# ProPrj_Arduino_DengDog_2025-10-27.net
KiCad netlist of a schematic drawn in EasyEDA Pro
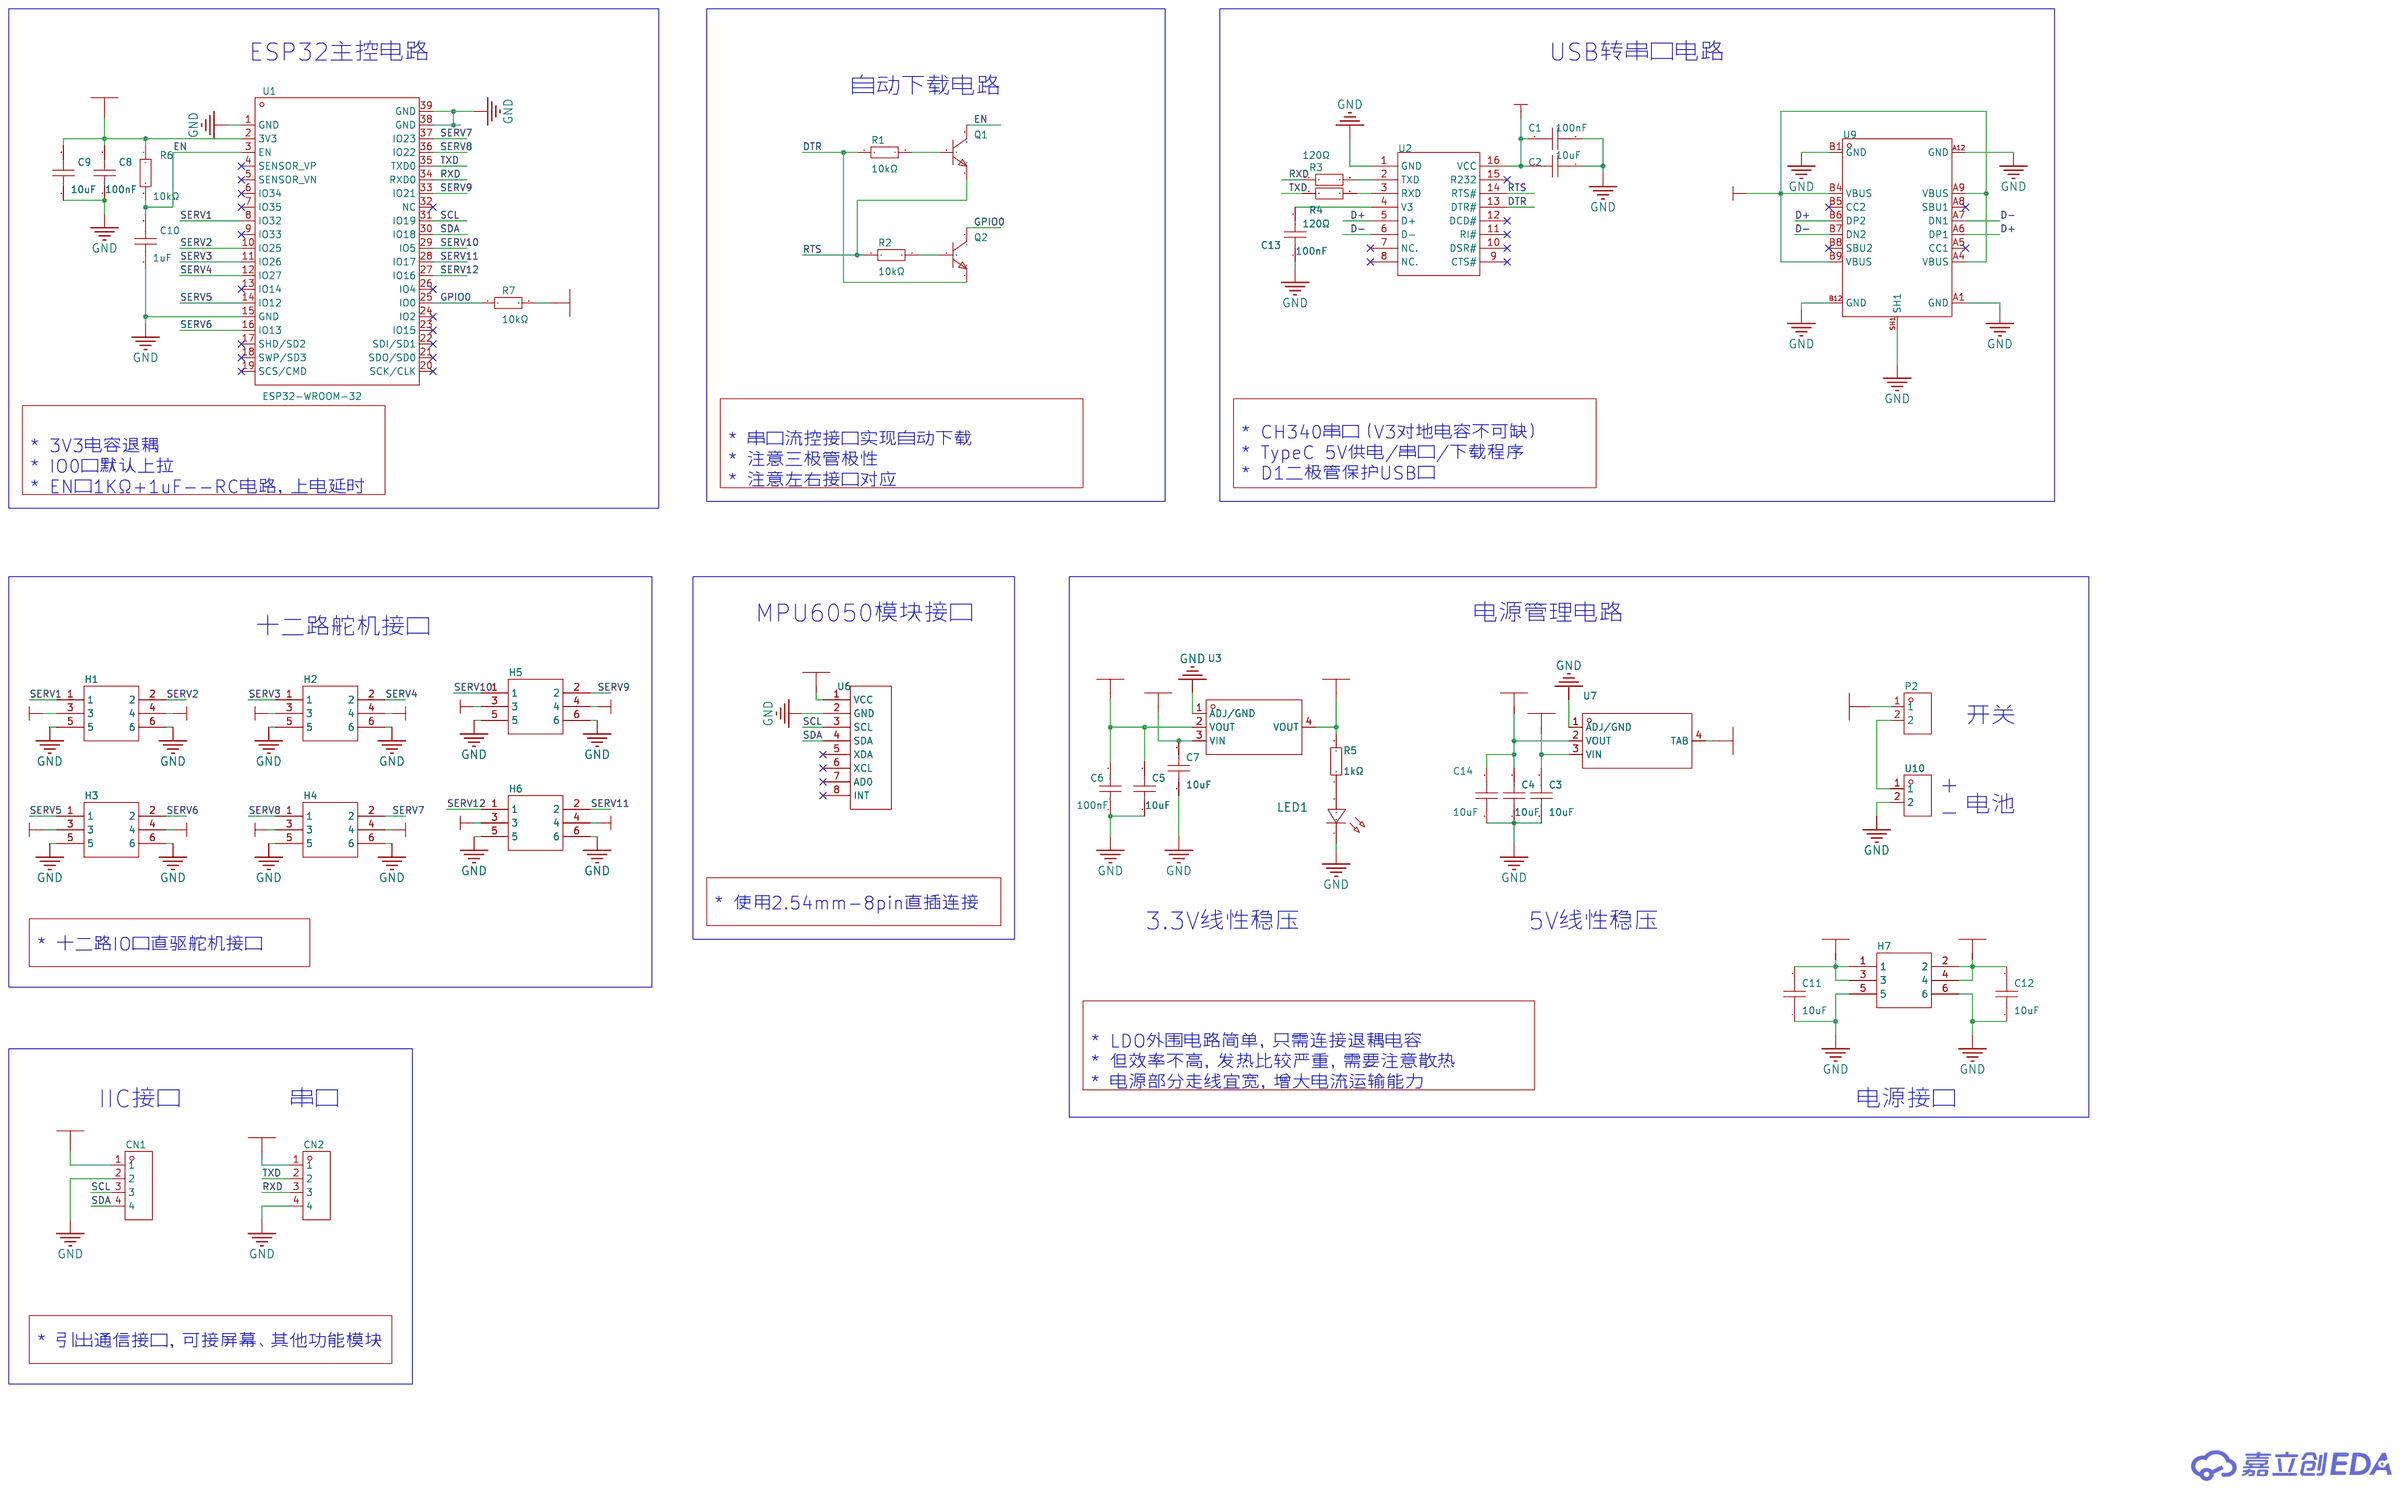
[diagram p0: schematic sheet]

(export (version "E")
  (design (tool "Eeschema 10.0.6"))
  (components
    (comp (ref "C1")
      (value "100nF")
      (fields
        (field (name "Manufacturer Part") "CC0603KRX7R9BB104")
        (field (name "Manufacturer") "YAGEO(国巨)")
      )
      (libsource (lib "easyedapro") (part "C1210X7R475K630NT"))
    )
    (comp (ref "C2")
      (value "10uF")
      (fields
        (field (name "Manufacturer Part") "CL10A106KP8NNNC")
        (field (name "Manufacturer") "SAMSUNG(三星)")
      )
      (libsource (lib "easyedapro") (part "C1210X7R475K630NT"))
    )
    (comp (ref "C3")
      (value "10uF")
      (fields
        (field (name "Manufacturer Part") "CL10A106KP8NNNC")
        (field (name "Manufacturer") "SAMSUNG(三星)")
      )
      (libsource (lib "easyedapro") (part "C1210X7R475K630NT"))
    )
    (comp (ref "C4")
      (value "10uF")
      (fields
        (field (name "Manufacturer Part") "CL10A106KP8NNNC")
        (field (name "Manufacturer") "SAMSUNG(三星)")
      )
      (libsource (lib "easyedapro") (part "C1210X7R475K630NT"))
    )
    (comp (ref "C5")
      (value "10uF")
      (fields
        (field (name "Manufacturer Part") "CL10A106KP8NNNC")
        (field (name "Manufacturer") "SAMSUNG(三星)")
      )
      (libsource (lib "easyedapro") (part "C1210X7R475K630NT"))
    )
    (comp (ref "C6")
      (value "100nF")
      (fields
        (field (name "Manufacturer Part") "CC0603KRX7R9BB104")
        (field (name "Manufacturer") "YAGEO(国巨)")
      )
      (libsource (lib "easyedapro") (part "C1210X7R475K630NT"))
    )
    (comp (ref "C7")
      (value "10uF")
      (fields
        (field (name "Manufacturer Part") "CL10A106KP8NNNC")
        (field (name "Manufacturer") "SAMSUNG(三星)")
      )
      (libsource (lib "easyedapro") (part "C1210X7R475K630NT"))
    )
    (comp (ref "C8")
      (value "100nF")
      (fields
        (field (name "Manufacturer Part") "CC0603KRX7R9BB104")
        (field (name "Manufacturer") "YAGEO(国巨)")
      )
      (libsource (lib "easyedapro") (part "C1210X7R475K630NT"))
    )
    (comp (ref "C9")
      (value "10uF")
      (fields
        (field (name "Manufacturer Part") "CL10A106KP8NNNC")
        (field (name "Manufacturer") "SAMSUNG(三星)")
      )
      (libsource (lib "easyedapro") (part "C1210X7R475K630NT"))
    )
    (comp (ref "C10")
      (value "1uF")
      (fields
        (field (name "Manufacturer Part") "CL10A105KB8NNNC")
        (field (name "Manufacturer") "SAMSUNG(三星)")
      )
      (libsource (lib "easyedapro") (part "C1210X7R475K630NT"))
    )
    (comp (ref "C11")
      (value "10uF")
      (fields
        (field (name "Manufacturer Part") "CL10A106KP8NNNC")
        (field (name "Manufacturer") "SAMSUNG(三星)")
      )
      (libsource (lib "easyedapro") (part "C1210X7R475K630NT"))
    )
    (comp (ref "C12")
      (value "10uF")
      (fields
        (field (name "Manufacturer Part") "CL10A106KP8NNNC")
        (field (name "Manufacturer") "SAMSUNG(三星)")
      )
      (libsource (lib "easyedapro") (part "C1210X7R475K630NT"))
    )
    (comp (ref "C13")
      (value "100nF")
      (fields
        (field (name "Manufacturer Part") "CC0603KRX7R9BB104")
        (field (name "Manufacturer") "YAGEO(国巨)")
      )
      (libsource (lib "easyedapro") (part "C1210X7R475K630NT"))
    )
    (comp (ref "C14")
      (value "10uF")
      (fields
        (field (name "Manufacturer Part") "CL10A106KP8NNNC")
        (field (name "Manufacturer") "SAMSUNG(三星)")
      )
      (libsource (lib "easyedapro") (part "C1210X7R475K630NT"))
    )
    (comp (ref "CN1")
      (value "A2541WV-4P")
      (footprint "easyedapro:HDR-TH_4P-P2.54-V-M")
      (fields (field (name "Manufacturer") "CJT(长江连接器)"))
      (libsource (lib "easyedapro") (part "A2541WV-4P_C5346656"))
    )
    (comp (ref "CN2")
      (value "A2541WV-4P")
      (footprint "easyedapro:HDR-TH_4P-P2.54-V-M")
      (fields (field (name "Manufacturer") "CJT(长江连接器)"))
      (libsource (lib "easyedapro") (part "A2541WV-4P_C5346656"))
    )
    (comp (ref "H1")
      (value "A2541WV-2x3P")
      (footprint "easyedapro:HDR-TH_6P-P2.54-V-R2-C3-S2.54_A2541WV-2X3P")
      (fields (field (name "Manufacturer") "CJT(长江连接器)"))
      (libsource (lib "easyedapro") (part "A2541WV-2X3P"))
    )
    (comp (ref "H2")
      (value "A2541WV-2x3P")
      (footprint "easyedapro:HDR-TH_6P-P2.54-V-R2-C3-S2.54_A2541WV-2X3P")
      (fields (field (name "Manufacturer") "CJT(长江连接器)"))
      (libsource (lib "easyedapro") (part "A2541WV-2X3P"))
    )
    (comp (ref "H3")
      (value "A2541WV-2x3P")
      (footprint "easyedapro:HDR-TH_6P-P2.54-V-R2-C3-S2.54_A2541WV-2X3P")
      (fields (field (name "Manufacturer") "CJT(长江连接器)"))
      (libsource (lib "easyedapro") (part "A2541WV-2X3P"))
    )
    (comp (ref "H4")
      (value "A2541WV-2x3P")
      (footprint "easyedapro:HDR-TH_6P-P2.54-V-R2-C3-S2.54_A2541WV-2X3P")
      (fields (field (name "Manufacturer") "CJT(长江连接器)"))
      (libsource (lib "easyedapro") (part "A2541WV-2X3P"))
    )
    (comp (ref "H5")
      (value "A2541WV-2x3P")
      (footprint "easyedapro:HDR-TH_6P-P2.54-V-R2-C3-S2.54_A2541WV-2X3P")
      (fields (field (name "Manufacturer") "CJT(长江连接器)"))
      (libsource (lib "easyedapro") (part "A2541WV-2X3P"))
    )
    (comp (ref "H6")
      (value "A2541WV-2x3P")
      (footprint "easyedapro:HDR-TH_6P-P2.54-V-R2-C3-S2.54_A2541WV-2X3P")
      (fields (field (name "Manufacturer") "CJT(长江连接器)"))
      (libsource (lib "easyedapro") (part "A2541WV-2X3P"))
    )
    (comp (ref "H7")
      (value "A2541WV-2x3P")
      (footprint "easyedapro:HDR-TH_6P-P2.54-V-R2-C3-S2.54_A2541WV-2X3P")
      (fields (field (name "Manufacturer") "CJT(长江连接器)"))
      (libsource (lib "easyedapro") (part "A2541WV-2X3P"))
    )
    (comp (ref "LED1")
      (value "19-217/R6C-AL1M2VY/3T")
      (fields (field (name "Manufacturer") "EVERLIGHT(亿光)"))
      (libsource (lib "easyedapro") (part "LED_R"))
    )
    (comp (ref "P2")
      (value "KF301-5.0-2P")
      (footprint "easyedapro:CONN-TH_EK508V-02P")
      (fields (field (name "Manufacturer") "KEFA(科发)"))
      (libsource (lib "easyedapro") (part "EK508V-02P_C9900003719"))
    )
    (comp (ref "Q1")
      (value "2N3904S-RTK/PS")
      (fields (field (name "Manufacturer") "KEC"))
      (libsource (lib "easyedapro") (part "2N3904(SOT-23)"))
    )
    (comp (ref "Q2")
      (value "2N3904S-RTK/PS")
      (fields (field (name "Manufacturer") "KEC"))
      (libsource (lib "easyedapro") (part "2N3904(SOT-23)"))
    )
    (comp (ref "R1")
      (value "10kΩ")
      (fields
        (field (name "Manufacturer Part") "0603WAF1002T5E")
        (field (name "Manufacturer") "UNI-ROYAL(厚声)")
      )
      (libsource (lib "easyedapro") (part "电阻"))
    )
    (comp (ref "R2")
      (value "10kΩ")
      (fields
        (field (name "Manufacturer Part") "0603WAF1002T5E")
        (field (name "Manufacturer") "UNI-ROYAL(厚声)")
      )
      (libsource (lib "easyedapro") (part "电阻"))
    )
    (comp (ref "R3")
      (value "120Ω")
      (fields
        (field (name "Manufacturer Part") "0603WAF1200T5E")
        (field (name "Manufacturer") "UNI-ROYAL(厚声)")
      )
      (libsource (lib "easyedapro") (part "电阻"))
    )
    (comp (ref "R4")
      (value "120Ω")
      (fields
        (field (name "Manufacturer Part") "0603WAF1200T5E")
        (field (name "Manufacturer") "UNI-ROYAL(厚声)")
      )
      (libsource (lib "easyedapro") (part "电阻"))
    )
    (comp (ref "R5")
      (value "1kΩ")
      (fields
        (field (name "Manufacturer Part") "0603WAF1001T5E")
        (field (name "Manufacturer") "UNI-ROYAL(厚声)")
      )
      (libsource (lib "easyedapro") (part "电阻"))
    )
    (comp (ref "R6")
      (value "10kΩ")
      (fields
        (field (name "Manufacturer Part") "0603WAF1002T5E")
        (field (name "Manufacturer") "UNI-ROYAL(厚声)")
      )
      (libsource (lib "easyedapro") (part "电阻"))
    )
    (comp (ref "R7")
      (value "10kΩ")
      (fields
        (field (name "Manufacturer Part") "0603WAF1002T5E")
        (field (name "Manufacturer") "UNI-ROYAL(厚声)")
      )
      (libsource (lib "easyedapro") (part "电阻"))
    )
    (comp (ref "U1")
      (value "ESP32-WROOM-32")
      (footprint "easyedapro:WIFIM-SMD_ESP-32S")
      (libsource (lib "easyedapro") (part "ESP32-WROOM-32"))
    )
    (comp (ref "U2")
      (value "CH340C")
      (fields (field (name "Manufacturer") "WCH(南京沁恒)"))
      (libsource (lib "easyedapro") (part "CH340C"))
    )
    (comp (ref "U3")
      (value "AMS1117-3.3")
      (fields (field (name "Manufacturer") "AMS"))
      (libsource (lib "easyedapro") (part "AMS1117-3.3V"))
    )
    (comp (ref "U6")
      (value "~")
      (footprint "easyedapro:MPU6050")
      (libsource (lib "easyedapro") (part "MPU6050"))
    )
    (comp (ref "U7")
      (value "~")
      (footprint "easyedapro:TO-263-3_L8.6-W10.2-P2.54-LS14.4-TL")
      (description "输出类型:固定;输出极性:正;输出通道数:1;最大输入电压:12V;输出电压:5V;压差:1.5V@(5A);输出电流:5A;电源纹波抑制比(PRSS):72dB@(120Hz);")
      (fields (field (name "Manufacturer Part") "LM1084S-5.0/TR") (field (name "Manufacturer") "HGSEMI(华冠)"))
      (libsource (lib "easyedapro") (part "LM1084S-5.0/TR"))
    )
    (comp (ref "U9")
      (value "U263-163N-4OS1735")
      (footprint "easyedapro:USB-C-SMD_U263-163N-4GS1735")
      (fields (field (name "Manufacturer") "XKB Connectivity(中国星坤)"))
      (libsource (lib "easyedapro") (part "U263-163N-4OS1735"))
    )
    (comp (ref "U10")
      (value "KF301-5.0-2P")
      (footprint "easyedapro:CONN-TH_P5.00_KF301-5.0-2P")
      (description "间距:5mm;排数:1;每排PIN数:2;安装方式:直针;额定电流:17A;额定电压:250V;线规 - AWG:14~22;线规 - mm?:1.5;工作温度范围:-30~+120;颜色:蓝色;")
      (fields (field (name "Manufacturer") "KEFA(科发)"))
      (libsource (lib "easyedapro") (part "KF301-5.0-2P"))
    )
  )
  (nets
    (net (code "1") (name "/D+") (class "Default")
      (node (ref "U2") (pin "5") (pinfunction "D+_5") (pintype "unspecified"))
      (node (ref "U9") (pin "A6") (pinfunction "DP1_A6") (pintype "input"))
      (node (ref "U9") (pin "B6") (pinfunction "DP2_B6") (pintype "input"))
    )
    (net (code "2") (name "/D-") (class "Default")
      (node (ref "U2") (pin "6") (pinfunction "D-_6") (pintype "unspecified"))
      (node (ref "U9") (pin "A7") (pinfunction "DN1_A7") (pintype "input"))
      (node (ref "U9") (pin "B7") (pinfunction "DN2_B7") (pintype "input"))
    )
    (net (code "3") (name "/DTR") (class "Default")
      (node (ref "Q2") (pin "1") (pinfunction "E_1") (pintype "input"))
      (node (ref "R1") (pin "1") (pinfunction "1_1") (pintype "input"))
      (node (ref "U2") (pin "13") (pinfunction "DTR#_13") (pintype "unspecified"))
    )
    (net (code "4") (name "/EN") (class "Default")
      (node (ref "C10") (pin "2") (pinfunction "2_2") (pintype "input"))
      (node (ref "Q1") (pin "3") (pinfunction "C_3") (pintype "input"))
      (node (ref "R6") (pin "2") (pinfunction "2_2") (pintype "input"))
      (node (ref "U1") (pin "3") (pinfunction "EN_3") (pintype "unspecified"))
    )
    (net (code "5") (name "/GPIO0") (class "Default")
      (node (ref "Q2") (pin "3") (pinfunction "C_3") (pintype "input"))
      (node (ref "R7") (pin "1") (pinfunction "1_1") (pintype "input"))
      (node (ref "U1") (pin "25") (pinfunction "IO0_25") (pintype "unspecified"))
    )
    (net (code "6") (name "/RTS") (class "Default")
      (node (ref "Q1") (pin "1") (pinfunction "E_1") (pintype "input"))
      (node (ref "R2") (pin "1") (pinfunction "1_1") (pintype "input"))
      (node (ref "U2") (pin "14") (pinfunction "RTS#_14") (pintype "unspecified"))
    )
    (net (code "7") (name "/RXD") (class "Default")
      (node (ref "CN2") (pin "3") (pinfunction "3_3") (pintype "input"))
      (node (ref "R3") (pin "1") (pinfunction "1_1") (pintype "input"))
      (node (ref "U1") (pin "34") (pinfunction "RXD0_34") (pintype "unspecified"))
    )
    (net (code "8") (name "/SCL") (class "Default")
      (node (ref "CN1") (pin "3") (pinfunction "3_3") (pintype "input"))
      (node (ref "U1") (pin "31") (pinfunction "IO19_31") (pintype "unspecified"))
      (node (ref "U6") (pin "3") (pinfunction "SCL_3") (pintype "input"))
    )
    (net (code "9") (name "/SDA") (class "Default")
      (node (ref "CN1") (pin "4") (pinfunction "4_4") (pintype "input"))
      (node (ref "U1") (pin "30") (pinfunction "IO18_30") (pintype "unspecified"))
      (node (ref "U6") (pin "4") (pinfunction "SDA_4") (pintype "input"))
    )
    (net (code "10") (name "/SERV1") (class "Default")
      (node (ref "H1") (pin "1") (pinfunction "1_1") (pintype "input"))
      (node (ref "U1") (pin "8") (pinfunction "IO32_8") (pintype "unspecified"))
    )
    (net (code "11") (name "/SERV2") (class "Default")
      (node (ref "H1") (pin "2") (pinfunction "2_2") (pintype "input"))
      (node (ref "U1") (pin "10") (pinfunction "IO25_10") (pintype "unspecified"))
    )
    (net (code "12") (name "/SERV3") (class "Default")
      (node (ref "H2") (pin "1") (pinfunction "1_1") (pintype "input"))
      (node (ref "U1") (pin "11") (pinfunction "IO26_11") (pintype "unspecified"))
    )
    (net (code "13") (name "/SERV4") (class "Default")
      (node (ref "H2") (pin "2") (pinfunction "2_2") (pintype "input"))
      (node (ref "U1") (pin "12") (pinfunction "IO27_12") (pintype "unspecified"))
    )
    (net (code "14") (name "/SERV5") (class "Default")
      (node (ref "H3") (pin "1") (pinfunction "1_1") (pintype "input"))
      (node (ref "U1") (pin "14") (pinfunction "IO12_14") (pintype "unspecified"))
    )
    (net (code "15") (name "/SERV6") (class "Default")
      (node (ref "H3") (pin "2") (pinfunction "2_2") (pintype "input"))
      (node (ref "U1") (pin "16") (pinfunction "IO13_16") (pintype "unspecified"))
    )
    (net (code "16") (name "/SERV7") (class "Default")
      (node (ref "H4") (pin "2") (pinfunction "2_2") (pintype "input"))
      (node (ref "U1") (pin "37") (pinfunction "IO23_37") (pintype "unspecified"))
    )
    (net (code "17") (name "/SERV8") (class "Default")
      (node (ref "H4") (pin "1") (pinfunction "1_1") (pintype "input"))
      (node (ref "U1") (pin "36") (pinfunction "IO22_36") (pintype "unspecified"))
    )
    (net (code "18") (name "/SERV9") (class "Default")
      (node (ref "H5") (pin "2") (pinfunction "2_2") (pintype "input"))
      (node (ref "U1") (pin "33") (pinfunction "IO21_33") (pintype "unspecified"))
    )
    (net (code "19") (name "/SERV10") (class "Default")
      (node (ref "H5") (pin "1") (pinfunction "1_1") (pintype "input"))
      (node (ref "U1") (pin "29") (pinfunction "IO5_29") (pintype "unspecified"))
    )
    (net (code "20") (name "/SERV11") (class "Default")
      (node (ref "H6") (pin "2") (pinfunction "2_2") (pintype "input"))
      (node (ref "U1") (pin "28") (pinfunction "IO17_28") (pintype "unspecified"))
    )
    (net (code "21") (name "/SERV12") (class "Default")
      (node (ref "H6") (pin "1") (pinfunction "1_1") (pintype "input"))
      (node (ref "U1") (pin "27") (pinfunction "IO16_27") (pintype "unspecified"))
    )
    (net (code "22") (name "/TXD") (class "Default")
      (node (ref "CN2") (pin "2") (pinfunction "2_2") (pintype "input"))
      (node (ref "R4") (pin "1") (pinfunction "1_1") (pintype "input"))
      (node (ref "U1") (pin "35") (pinfunction "TXD0_35") (pintype "unspecified"))
    )
    (net (code "23") (name "3V3") (class "Default")
      (node (ref "C11") (pin "2") (pinfunction "2_2") (pintype "input"))
      (node (ref "C5") (pin "2") (pinfunction "2_2") (pintype "input"))
      (node (ref "C6") (pin "2") (pinfunction "2_2") (pintype "input"))
      (node (ref "C8") (pin "2") (pinfunction "2_2") (pintype "input"))
      (node (ref "C9") (pin "2") (pinfunction "2_2") (pintype "input"))
      (node (ref "CN1") (pin "1") (pinfunction "1_1") (pintype "input"))
      (node (ref "H7") (pin "1") (pinfunction "1_1") (pintype "input"))
      (node (ref "H7") (pin "3") (pinfunction "3_3") (pintype "input"))
      (node (ref "R5") (pin "2") (pinfunction "2_2") (pintype "input"))
      (node (ref "R6") (pin "1") (pinfunction "1_1") (pintype "input"))
      (node (ref "R7") (pin "2") (pinfunction "2_2") (pintype "input"))
      (node (ref "U1") (pin "2") (pinfunction "3V3_2") (pintype "unspecified"))
      (node (ref "U3") (pin "2") (pinfunction "VOUT_2") (pintype "unspecified"))
      (node (ref "U3") (pin "4") (pinfunction "VOUT_4") (pintype "unspecified"))
      (node (ref "U6") (pin "1") (pinfunction "VCC_1") (pintype "input"))
    )
    (net (code "24") (name "5VIN") (class "Default")
      (node (ref "C1") (pin "1") (pinfunction "1_1") (pintype "input"))
      (node (ref "C12") (pin "2") (pinfunction "2_2") (pintype "input"))
      (node (ref "C14") (pin "2") (pinfunction "2_2") (pintype "input"))
      (node (ref "C2") (pin "1") (pinfunction "1_1") (pintype "input"))
      (node (ref "C4") (pin "2") (pinfunction "2_2") (pintype "input"))
      (node (ref "C7") (pin "2") (pinfunction "2_2") (pintype "input"))
      (node (ref "CN2") (pin "1") (pinfunction "1_1") (pintype "input"))
      (node (ref "H1") (pin "3") (pinfunction "3_3") (pintype "input"))
      (node (ref "H1") (pin "4") (pinfunction "4_4") (pintype "input"))
      (node (ref "H2") (pin "3") (pinfunction "3_3") (pintype "input"))
      (node (ref "H2") (pin "4") (pinfunction "4_4") (pintype "input"))
      (node (ref "H3") (pin "3") (pinfunction "3_3") (pintype "input"))
      (node (ref "H3") (pin "4") (pinfunction "4_4") (pintype "input"))
      (node (ref "H4") (pin "3") (pinfunction "3_3") (pintype "input"))
      (node (ref "H4") (pin "4") (pinfunction "4_4") (pintype "input"))
      (node (ref "H5") (pin "3") (pinfunction "3_3") (pintype "input"))
      (node (ref "H5") (pin "4") (pinfunction "4_4") (pintype "input"))
      (node (ref "H6") (pin "3") (pinfunction "3_3") (pintype "input"))
      (node (ref "H6") (pin "4") (pinfunction "4_4") (pintype "input"))
      (node (ref "H7") (pin "2") (pinfunction "2_2") (pintype "input"))
      (node (ref "H7") (pin "4") (pinfunction "4_4") (pintype "input"))
      (node (ref "U2") (pin "16") (pinfunction "VCC_16") (pintype "unspecified"))
      (node (ref "U3") (pin "3") (pinfunction "VIN_3") (pintype "unspecified"))
      (node (ref "U7") (pin "2") (pinfunction "VOUT_2") (pintype "input"))
      (node (ref "U7") (pin "4") (pinfunction "TAB_4") (pintype "input"))
      (node (ref "U9") (pin "A4") (pinfunction "VBUS_A4") (pintype "input"))
      (node (ref "U9") (pin "A9") (pinfunction "VBUS_A9") (pintype "input"))
      (node (ref "U9") (pin "B4") (pinfunction "VBUS_B4") (pintype "input"))
      (node (ref "U9") (pin "B9") (pinfunction "VBUS_B9") (pintype "input"))
    )
    (net (code "25") (name "GND") (class "Default")
      (node (ref "C1") (pin "2") (pinfunction "2_2") (pintype "input"))
      (node (ref "C10") (pin "1") (pinfunction "1_1") (pintype "input"))
      (node (ref "C11") (pin "1") (pinfunction "1_1") (pintype "input"))
      (node (ref "C12") (pin "1") (pinfunction "1_1") (pintype "input"))
      (node (ref "C13") (pin "1") (pinfunction "1_1") (pintype "input"))
      (node (ref "C14") (pin "1") (pinfunction "1_1") (pintype "input"))
      (node (ref "C2") (pin "2") (pinfunction "2_2") (pintype "input"))
      (node (ref "C3") (pin "1") (pinfunction "1_1") (pintype "input"))
      (node (ref "C4") (pin "1") (pinfunction "1_1") (pintype "input"))
      (node (ref "C5") (pin "1") (pinfunction "1_1") (pintype "input"))
      (node (ref "C6") (pin "1") (pinfunction "1_1") (pintype "input"))
      (node (ref "C7") (pin "1") (pinfunction "1_1") (pintype "input"))
      (node (ref "C8") (pin "1") (pinfunction "1_1") (pintype "input"))
      (node (ref "C9") (pin "1") (pinfunction "1_1") (pintype "input"))
      (node (ref "CN1") (pin "2") (pinfunction "2_2") (pintype "input"))
      (node (ref "CN2") (pin "4") (pinfunction "4_4") (pintype "input"))
      (node (ref "H1") (pin "5") (pinfunction "5_5") (pintype "input"))
      (node (ref "H1") (pin "6") (pinfunction "6_6") (pintype "input"))
      (node (ref "H2") (pin "5") (pinfunction "5_5") (pintype "input"))
      (node (ref "H2") (pin "6") (pinfunction "6_6") (pintype "input"))
      (node (ref "H3") (pin "5") (pinfunction "5_5") (pintype "input"))
      (node (ref "H3") (pin "6") (pinfunction "6_6") (pintype "input"))
      (node (ref "H4") (pin "5") (pinfunction "5_5") (pintype "input"))
      (node (ref "H4") (pin "6") (pinfunction "6_6") (pintype "input"))
      (node (ref "H5") (pin "5") (pinfunction "5_5") (pintype "input"))
      (node (ref "H5") (pin "6") (pinfunction "6_6") (pintype "input"))
      (node (ref "H6") (pin "5") (pinfunction "5_5") (pintype "input"))
      (node (ref "H6") (pin "6") (pinfunction "6_6") (pintype "input"))
      (node (ref "H7") (pin "5") (pinfunction "5_5") (pintype "input"))
      (node (ref "H7") (pin "6") (pinfunction "6_6") (pintype "input"))
      (node (ref "LED1") (pin "1") (pinfunction "C_1") (pintype "input"))
      (node (ref "U1") (pin "1") (pinfunction "GND_1") (pintype "unspecified"))
      (node (ref "U1") (pin "15") (pinfunction "GND_15") (pintype "unspecified"))
      (node (ref "U1") (pin "38") (pinfunction "GND_38") (pintype "unspecified"))
      (node (ref "U1") (pin "39") (pinfunction "GND_39") (pintype "unspecified"))
      (node (ref "U10") (pin "2") (pinfunction "2_2") (pintype "input"))
      (node (ref "U2") (pin "1") (pinfunction "GND_1") (pintype "unspecified"))
      (node (ref "U3") (pin "1") (pinfunction "ADJ/GND_1") (pintype "unspecified"))
      (node (ref "U6") (pin "2") (pinfunction "GND_2") (pintype "input"))
      (node (ref "U7") (pin "1") (pinfunction "ADJ/GND_1") (pintype "input"))
      (node (ref "U9") (pin "A1") (pinfunction "GND_A1") (pintype "input"))
      (node (ref "U9") (pin "A12") (pinfunction "GND_A12") (pintype "input"))
      (node (ref "U9") (pin "B1") (pinfunction "GND_B1") (pintype "input"))
      (node (ref "U9") (pin "B12") (pinfunction "GND_B12") (pintype "input"))
      (node (ref "U9") (pin "SH1") (pinfunction "SH1_SH1") (pintype "input"))
    )
    (net (code "26") (name "Net-(LED1-A)") (class "Default")
      (node (ref "LED1") (pin "2") (pinfunction "A_2") (pintype "input"))
      (node (ref "R5") (pin "1") (pinfunction "1_1") (pintype "input"))
    )
    (net (code "27") (name "Net-(P2-Pad2)") (class "Default")
      (node (ref "P2") (pin "2") (pinfunction "2_2") (pintype "input"))
      (node (ref "U10") (pin "1") (pinfunction "1_1") (pintype "input"))
    )
    (net (code "28") (name "Net-(Q1-B)") (class "Default")
      (node (ref "Q1") (pin "2") (pinfunction "B_2") (pintype "input"))
      (node (ref "R1") (pin "2") (pinfunction "2_2") (pintype "input"))
    )
    (net (code "29") (name "Net-(Q2-B)") (class "Default")
      (node (ref "Q2") (pin "2") (pinfunction "B_2") (pintype "input"))
      (node (ref "R2") (pin "2") (pinfunction "2_2") (pintype "input"))
    )
    (net (code "30") (name "Net-(U2-RXD)") (class "Default")
      (node (ref "R4") (pin "2") (pinfunction "2_2") (pintype "input"))
      (node (ref "U2") (pin "3") (pinfunction "RXD_3") (pintype "unspecified"))
    )
    (net (code "31") (name "Net-(U2-TXD)") (class "Default")
      (node (ref "R3") (pin "2") (pinfunction "2_2") (pintype "input"))
      (node (ref "U2") (pin "2") (pinfunction "TXD_2") (pintype "unspecified"))
    )
    (net (code "32") (name "Net-(U2-V3)") (class "Default")
      (node (ref "C13") (pin "2") (pinfunction "2_2") (pintype "input"))
      (node (ref "U2") (pin "4") (pinfunction "V3_4") (pintype "unspecified"))
    )
    (net (code "33") (name "VIN") (class "Default")
      (node (ref "C3") (pin "2") (pinfunction "2_2") (pintype "input"))
      (node (ref "P2") (pin "1") (pinfunction "1_1") (pintype "input"))
      (node (ref "U7") (pin "3") (pinfunction "VIN_3") (pintype "input"))
    )
    (net (code "34") (name "unconnected-(U1-IO2-Pad24)") (class "Default")
      (node (ref "U1") (pin "24") (pinfunction "IO2_24") (pintype "unspecified+no_connect"))
    )
    (net (code "35") (name "unconnected-(U1-IO4-Pad26)") (class "Default")
      (node (ref "U1") (pin "26") (pinfunction "IO4_26") (pintype "unspecified+no_connect"))
    )
    (net (code "36") (name "unconnected-(U1-IO14-Pad13)") (class "Default")
      (node (ref "U1") (pin "13") (pinfunction "IO14_13") (pintype "unspecified+no_connect"))
    )
    (net (code "37") (name "unconnected-(U1-IO15-Pad23)") (class "Default")
      (node (ref "U1") (pin "23") (pinfunction "IO15_23") (pintype "unspecified+no_connect"))
    )
    (net (code "38") (name "unconnected-(U1-IO33-Pad9)") (class "Default")
      (node (ref "U1") (pin "9") (pinfunction "IO33_9") (pintype "unspecified+no_connect"))
    )
    (net (code "39") (name "unconnected-(U1-IO34-Pad6)") (class "Default")
      (node (ref "U1") (pin "6") (pinfunction "IO34_6") (pintype "unspecified+no_connect"))
    )
    (net (code "40") (name "unconnected-(U1-IO35-Pad7)") (class "Default")
      (node (ref "U1") (pin "7") (pinfunction "IO35_7") (pintype "unspecified+no_connect"))
    )
    (net (code "41") (name "unconnected-(U1-NC-Pad32)") (class "Default")
      (node (ref "U1") (pin "32") (pinfunction "NC_32") (pintype "unspecified+no_connect"))
    )
    (net (code "42") (name "unconnected-(U1-SCK{slash}CLK-Pad20)") (class "Default")
      (node (ref "U1") (pin "20") (pinfunction "SCK/CLK_20") (pintype "unspecified+no_connect"))
    )
    (net (code "43") (name "unconnected-(U1-SCS{slash}CMD-Pad19)") (class "Default")
      (node (ref "U1") (pin "19") (pinfunction "SCS/CMD_19") (pintype "unspecified+no_connect"))
    )
    (net (code "44") (name "unconnected-(U1-SDI{slash}SD1-Pad22)") (class "Default")
      (node (ref "U1") (pin "22") (pinfunction "SDI/SD1_22") (pintype "unspecified+no_connect"))
    )
    (net (code "45") (name "unconnected-(U1-SDO{slash}SD0-Pad21)") (class "Default")
      (node (ref "U1") (pin "21") (pinfunction "SDO/SD0_21") (pintype "unspecified+no_connect"))
    )
    (net (code "46") (name "unconnected-(U1-SENSOR_VN-Pad5)") (class "Default")
      (node (ref "U1") (pin "5") (pinfunction "SENSOR_VN_5") (pintype "unspecified+no_connect"))
    )
    (net (code "47") (name "unconnected-(U1-SENSOR_VP-Pad4)") (class "Default")
      (node (ref "U1") (pin "4") (pinfunction "SENSOR_VP_4") (pintype "unspecified+no_connect"))
    )
    (net (code "48") (name "unconnected-(U1-SHD{slash}SD2-Pad17)") (class "Default")
      (node (ref "U1") (pin "17") (pinfunction "SHD/SD2_17") (pintype "unspecified+no_connect"))
    )
    (net (code "49") (name "unconnected-(U1-SWP{slash}SD3-Pad18)") (class "Default")
      (node (ref "U1") (pin "18") (pinfunction "SWP/SD3_18") (pintype "unspecified+no_connect"))
    )
    (net (code "50") (name "unconnected-(U2-CTS#-Pad9)") (class "Default")
      (node (ref "U2") (pin "9") (pinfunction "CTS#_9") (pintype "unspecified+no_connect"))
    )
    (net (code "51") (name "unconnected-(U2-DCD#-Pad12)") (class "Default")
      (node (ref "U2") (pin "12") (pinfunction "DCD#_12") (pintype "unspecified+no_connect"))
    )
    (net (code "52") (name "unconnected-(U2-DSR#-Pad10)") (class "Default")
      (node (ref "U2") (pin "10") (pinfunction "DSR#_10") (pintype "unspecified+no_connect"))
    )
    (net (code "53") (name "unconnected-(U2-NC.-Pad7)") (class "Default")
      (node (ref "U2") (pin "7") (pinfunction "NC._7") (pintype "unspecified+no_connect"))
    )
    (net (code "54") (name "unconnected-(U2-NC.-Pad8)") (class "Default")
      (node (ref "U2") (pin "8") (pinfunction "NC._8") (pintype "unspecified+no_connect"))
    )
    (net (code "55") (name "unconnected-(U2-R232-Pad15)") (class "Default")
      (node (ref "U2") (pin "15") (pinfunction "R232_15") (pintype "unspecified+no_connect"))
    )
    (net (code "56") (name "unconnected-(U2-RI#-Pad11)") (class "Default")
      (node (ref "U2") (pin "11") (pinfunction "RI#_11") (pintype "unspecified+no_connect"))
    )
    (net (code "57") (name "unconnected-(U6-AD0-Pad7)") (class "Default")
      (node (ref "U6") (pin "7") (pinfunction "AD0_7") (pintype "input+no_connect"))
    )
    (net (code "58") (name "unconnected-(U6-INT-Pad8)") (class "Default")
      (node (ref "U6") (pin "8") (pinfunction "INT_8") (pintype "input+no_connect"))
    )
    (net (code "59") (name "unconnected-(U6-XCL-Pad6)") (class "Default")
      (node (ref "U6") (pin "6") (pinfunction "XCL_6") (pintype "input+no_connect"))
    )
    (net (code "60") (name "unconnected-(U6-XDA-Pad5)") (class "Default")
      (node (ref "U6") (pin "5") (pinfunction "XDA_5") (pintype "input+no_connect"))
    )
    (net (code "61") (name "unconnected-(U9-CC1-PadA5)") (class "Default")
      (node (ref "U9") (pin "A5") (pinfunction "CC1_A5") (pintype "input+no_connect"))
    )
    (net (code "62") (name "unconnected-(U9-CC2-PadB5)") (class "Default")
      (node (ref "U9") (pin "B5") (pinfunction "CC2_B5") (pintype "input+no_connect"))
    )
    (net (code "63") (name "unconnected-(U9-SBU1-PadA8)") (class "Default")
      (node (ref "U9") (pin "A8") (pinfunction "SBU1_A8") (pintype "input+no_connect"))
    )
    (net (code "64") (name "unconnected-(U9-SBU2-PadB8)") (class "Default")
      (node (ref "U9") (pin "B8") (pinfunction "SBU2_B8") (pintype "input+no_connect"))
    )
  )
)
